# shrew-programmer.net
KiCad netlist of a schematic drawn in EAGLE
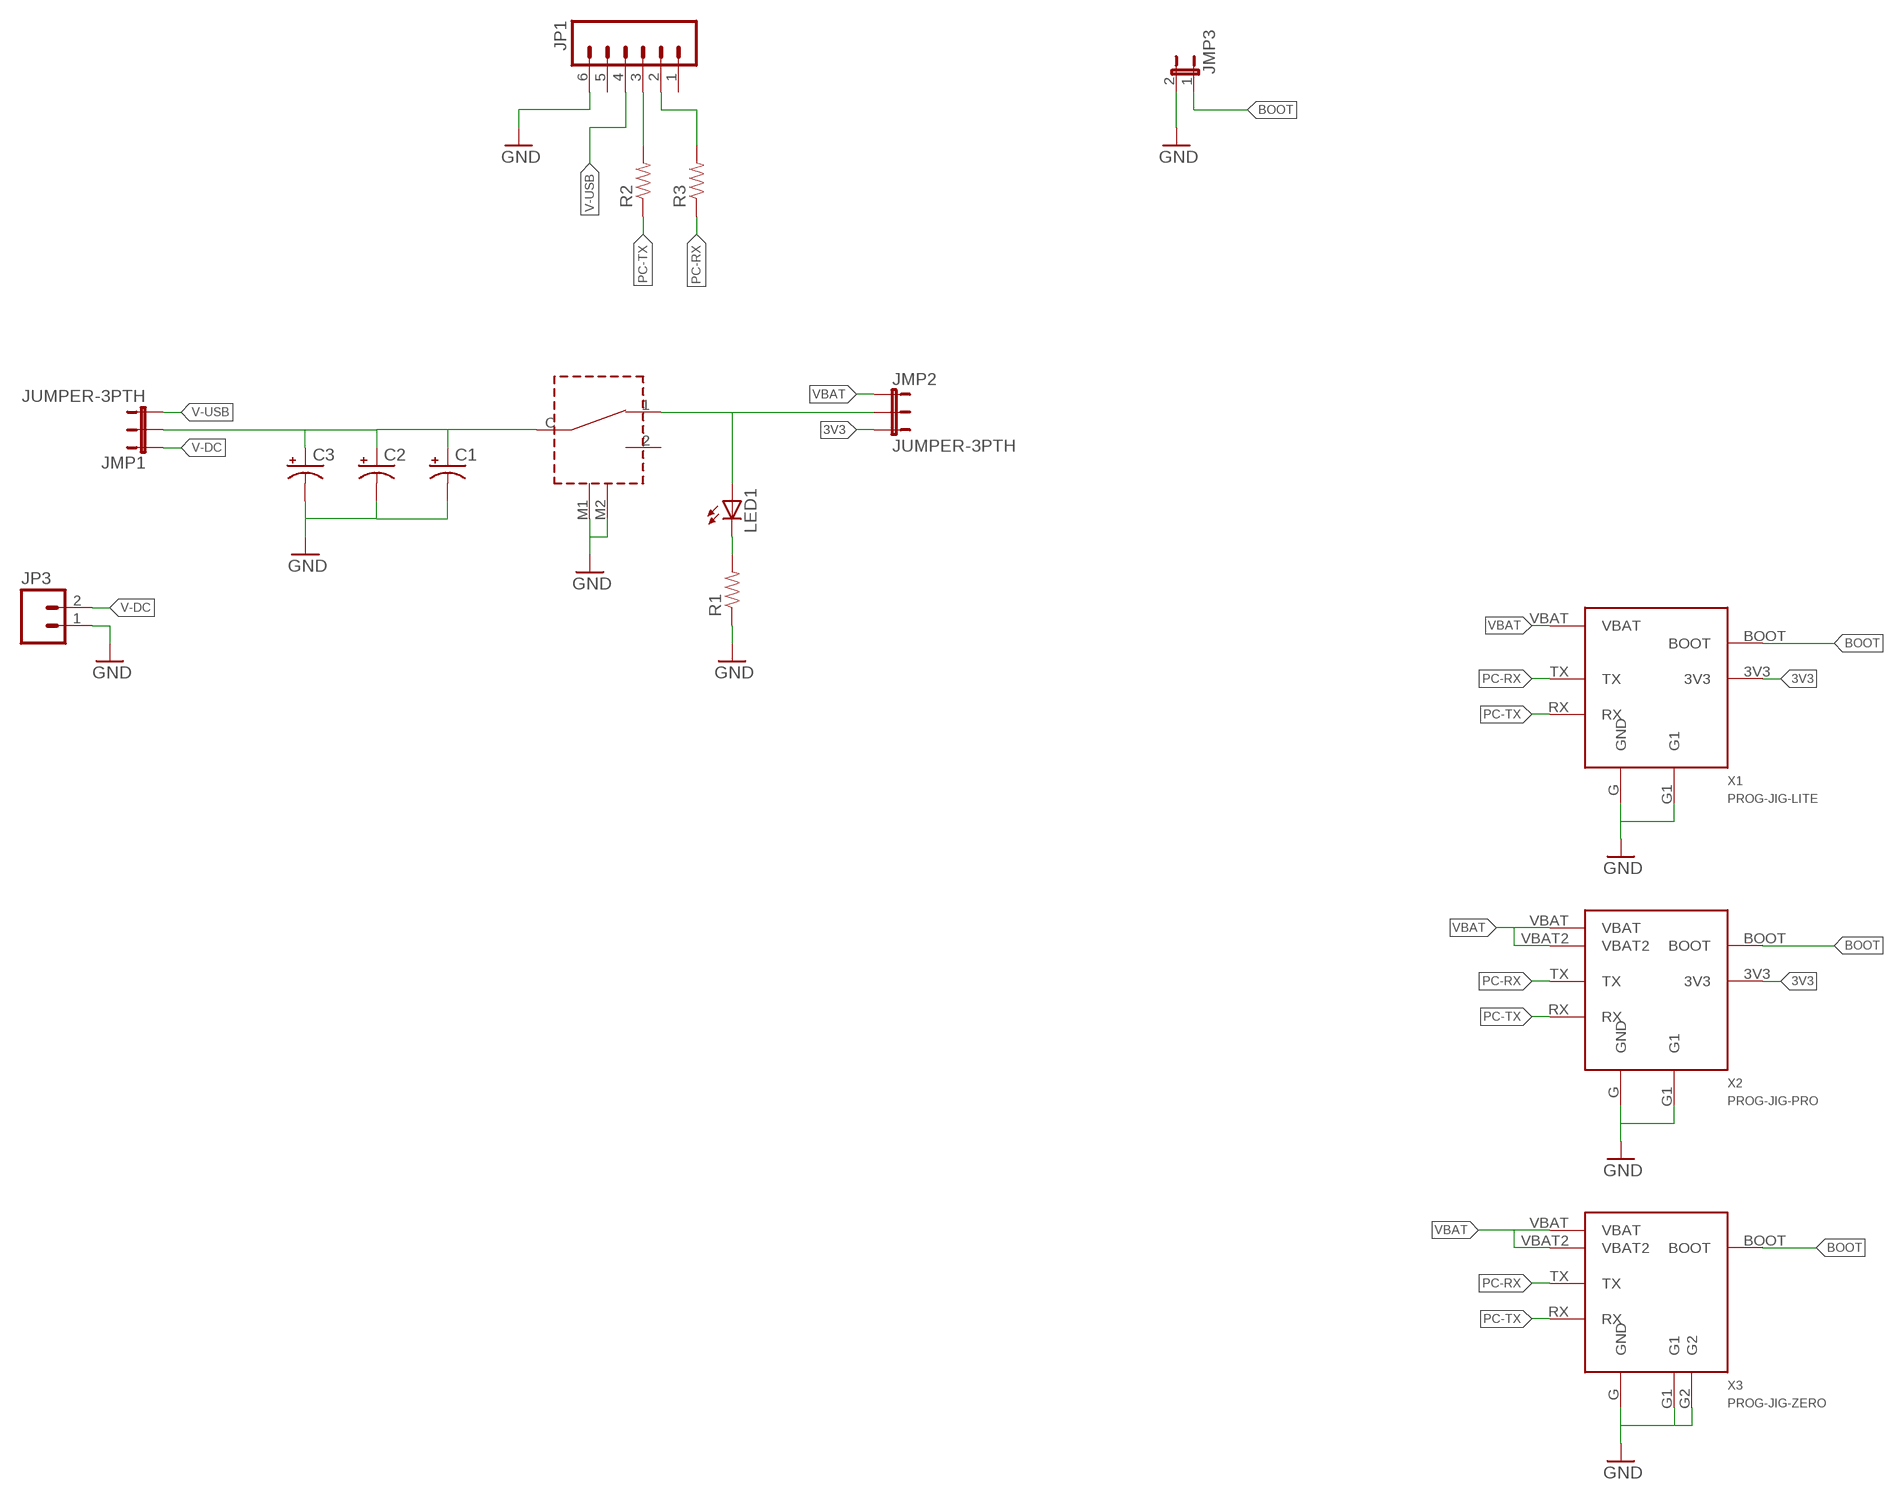
[diagram p0: schematic, sheet 1]

(export (version "E")
  (design (tool "Eeschema 10.0.6"))
  (components
    (comp (ref "C1")
      (value "CAP_POLPTH1")
      (footprint "eagle-import:CPOL-RADIAL-100UF-25V")
      (libsource (lib "eagle-import") (part "CAP_POLPTH1"))
    )
    (comp (ref "C2")
      (value "CAP_POLPTH1")
      (footprint "eagle-import:CPOL-RADIAL-100UF-25V")
      (libsource (lib "eagle-import") (part "CAP_POLPTH1"))
    )
    (comp (ref "C3")
      (value "CAP_POLPTH1")
      (footprint "eagle-import:CPOL-RADIAL-100UF-25V")
      (libsource (lib "eagle-import") (part "CAP_POLPTH1"))
    )
    (comp (ref "JMP1")
      (value "JUMPER-3PTH")
      (footprint "eagle-import:1X03")
      (libsource (lib "eagle-import") (part "JUMPER-3PTH"))
    )
    (comp (ref "JMP2")
      (value "JUMPER-3PTH")
      (footprint "eagle-import:1X03")
      (libsource (lib "eagle-import") (part "JUMPER-3PTH"))
    )
    (comp (ref "JMP3")
      (value "JUMPER-2PTH")
      (footprint "eagle-import:1X02")
      (libsource (lib "eagle-import") (part "JUMPER-2PTH"))
    )
    (comp (ref "JP1")
      (value "M06LONGPADS")
      (footprint "eagle-import:1X06_LONGPADS")
      (libsource (lib "eagle-import") (part "M06LONGPADS"))
    )
    (comp (ref "JP3")
      (value "M023.5MM")
      (footprint "eagle-import:SCREWTERMINAL-3.5MM-2")
      (libsource (lib "eagle-import") (part "M023.5MM"))
    )
    (comp (ref "LED1")
      (value "LED1206")
      (footprint "eagle-import:LED-1206")
      (libsource (lib "eagle-import") (part "LED1206"))
    )
    (comp (ref "R1")
      (value "RESISTOR0603-RES")
      (footprint "eagle-import:0603-RES")
      (libsource (lib "eagle-import") (part "RESISTOR0603-RES"))
    )
    (comp (ref "R2")
      (value "RESISTOR0603-RES")
      (footprint "eagle-import:0603-RES")
      (libsource (lib "eagle-import") (part "RESISTOR0603-RES"))
    )
    (comp (ref "R3")
      (value "RESISTOR0603-RES")
      (footprint "eagle-import:0603-RES")
      (libsource (lib "eagle-import") (part "RESISTOR0603-RES"))
    )
    (comp (ref "SW1")
      (value "SWITCH-ROCKER-3PIN-2MNT")
      (footprint "eagle-import:SWITCH-ROCKER-3PIN-2MNT")
      (libsource (lib "eagle-import") (part "SWITCH-ROCKER-3PIN-2MNT"))
    )
    (comp (ref "X1")
      (value "PROG-JIG-LITE")
      (footprint "eagle-import:PROG-JIG-LITE")
      (libsource (lib "eagle-import") (part "PROG-JIG-LITE"))
    )
    (comp (ref "X2")
      (value "PROG-JIG-PRO")
      (footprint "eagle-import:PROG-JIG-PRO")
      (libsource (lib "eagle-import") (part "PROG-JIG-PRO"))
    )
    (comp (ref "X3")
      (value "PROG-JIG-ZERO")
      (footprint "eagle-import:PROG-JIG-ZERO")
      (libsource (lib "eagle-import") (part "PROG-JIG-ZERO"))
    )
  )
  (nets
    (net (code "1") (name "3V3") (class "Default")
      (node (ref "JMP2") (pin "3") (pinfunction "3_3") (pintype "passive"))
      (node (ref "X1") (pin "3V3") (pinfunction "3V3_3V3") (pintype "bidirectional"))
      (node (ref "X2") (pin "3V3") (pinfunction "3V3_3V3") (pintype "bidirectional"))
    )
    (net (code "2") (name "BOOT") (class "Default")
      (node (ref "JMP3") (pin "1") (pinfunction "1_1") (pintype "passive"))
      (node (ref "X1") (pin "BOOT") (pinfunction "BOOT_BOOT") (pintype "bidirectional"))
      (node (ref "X2") (pin "BOOT") (pinfunction "BOOT_BOOT") (pintype "bidirectional"))
      (node (ref "X3") (pin "BOOT") (pinfunction "BOOT_BOOT") (pintype "bidirectional"))
    )
    (net (code "3") (name "GND") (class "Default")
      (node (ref "C1") (pin "2") (pinfunction "-_2") (pintype "passive"))
      (node (ref "C2") (pin "2") (pinfunction "-_2") (pintype "passive"))
      (node (ref "C3") (pin "2") (pinfunction "-_2") (pintype "passive"))
      (node (ref "JMP3") (pin "2") (pinfunction "2_2") (pintype "passive"))
      (node (ref "JP1") (pin "6") (pinfunction "6_6") (pintype "passive"))
      (node (ref "JP3") (pin "1") (pinfunction "1_1") (pintype "passive"))
      (node (ref "R1") (pin "1") (pinfunction "1_1") (pintype "passive"))
      (node (ref "SW1") (pin "M1") (pinfunction "M1_M1") (pintype "bidirectional"))
      (node (ref "SW1") (pin "M2") (pinfunction "M2_M2") (pintype "bidirectional"))
      (node (ref "X1") (pin "G") (pinfunction "GND_G") (pintype "bidirectional"))
      (node (ref "X1") (pin "G1") (pinfunction "G1_G1") (pintype "bidirectional"))
      (node (ref "X2") (pin "G") (pinfunction "GND_G") (pintype "bidirectional"))
      (node (ref "X2") (pin "G1") (pinfunction "G1_G1") (pintype "bidirectional"))
      (node (ref "X3") (pin "G") (pinfunction "GND_G") (pintype "bidirectional"))
      (node (ref "X3") (pin "G1") (pinfunction "G1_G1") (pintype "bidirectional"))
      (node (ref "X3") (pin "G2") (pinfunction "G2_G2") (pintype "bidirectional"))
    )
    (net (code "4") (name "Net-(C1-+)") (class "Default")
      (node (ref "C1") (pin "1") (pinfunction "+_1") (pintype "passive"))
      (node (ref "C2") (pin "1") (pinfunction "+_1") (pintype "passive"))
      (node (ref "C3") (pin "1") (pinfunction "+_1") (pintype "passive"))
      (node (ref "JMP1") (pin "2") (pinfunction "2_2") (pintype "passive"))
      (node (ref "SW1") (pin "C") (pinfunction "C_C") (pintype "bidirectional"))
    )
    (net (code "5") (name "Net-(JMP2-Pad2)") (class "Default")
      (node (ref "JMP2") (pin "2") (pinfunction "2_2") (pintype "passive"))
      (node (ref "LED1") (pin "A") (pinfunction "A_A") (pintype "passive"))
      (node (ref "SW1") (pin "1") (pinfunction "1_1") (pintype "bidirectional"))
    )
    (net (code "6") (name "Net-(JP1-Pad2)") (class "Default")
      (node (ref "JP1") (pin "2") (pinfunction "2_2") (pintype "passive"))
      (node (ref "R3") (pin "2") (pinfunction "2_2") (pintype "passive"))
    )
    (net (code "7") (name "Net-(JP1-Pad3)") (class "Default")
      (node (ref "JP1") (pin "3") (pinfunction "3_3") (pintype "passive"))
      (node (ref "R2") (pin "2") (pinfunction "2_2") (pintype "passive"))
    )
    (net (code "8") (name "Net-(LED1-PadC)") (class "Default")
      (node (ref "LED1") (pin "C") (pinfunction "C_C") (pintype "passive"))
      (node (ref "R1") (pin "2") (pinfunction "2_2") (pintype "passive"))
    )
    (net (code "9") (name "PC-RX") (class "Default")
      (node (ref "R3") (pin "1") (pinfunction "1_1") (pintype "passive"))
      (node (ref "X1") (pin "TX") (pinfunction "TX_TX") (pintype "bidirectional"))
      (node (ref "X2") (pin "TX") (pinfunction "TX_TX") (pintype "bidirectional"))
      (node (ref "X3") (pin "TX") (pinfunction "TX_TX") (pintype "bidirectional"))
    )
    (net (code "10") (name "PC-TX") (class "Default")
      (node (ref "R2") (pin "1") (pinfunction "1_1") (pintype "passive"))
      (node (ref "X1") (pin "RX") (pinfunction "RX_RX") (pintype "bidirectional"))
      (node (ref "X2") (pin "RX") (pinfunction "RX_RX") (pintype "bidirectional"))
      (node (ref "X3") (pin "RX") (pinfunction "RX_RX") (pintype "bidirectional"))
    )
    (net (code "11") (name "V-DC") (class "Default")
      (node (ref "JMP1") (pin "1") (pinfunction "1_1") (pintype "passive"))
      (node (ref "JP3") (pin "2") (pinfunction "2_2") (pintype "passive"))
    )
    (net (code "12") (name "V-USB") (class "Default")
      (node (ref "JMP1") (pin "3") (pinfunction "3_3") (pintype "passive"))
      (node (ref "JP1") (pin "4") (pinfunction "4_4") (pintype "passive"))
    )
    (net (code "13") (name "VBAT") (class "Default")
      (node (ref "JMP2") (pin "1") (pinfunction "1_1") (pintype "passive"))
      (node (ref "X1") (pin "VBAT") (pinfunction "VBAT_VBAT") (pintype "bidirectional"))
      (node (ref "X2") (pin "VBAT") (pinfunction "VBAT_VBAT") (pintype "bidirectional"))
      (node (ref "X2") (pin "VBAT2") (pinfunction "VBAT2_VBAT2") (pintype "bidirectional"))
      (node (ref "X3") (pin "VBAT") (pinfunction "VBAT_VBAT") (pintype "bidirectional"))
      (node (ref "X3") (pin "VBAT2") (pinfunction "VBAT2_VBAT2") (pintype "bidirectional"))
    )
    (net (code "14") (name "unconnected-(JP1-Pad1)") (class "Default")
      (node (ref "JP1") (pin "1") (pinfunction "1_1") (pintype "passive"))
    )
    (net (code "15") (name "unconnected-(JP1-Pad5)") (class "Default")
      (node (ref "JP1") (pin "5") (pinfunction "5_5") (pintype "passive"))
    )
    (net (code "16") (name "unconnected-(SW1-Pad2)") (class "Default")
      (node (ref "SW1") (pin "2") (pinfunction "2_2") (pintype "bidirectional"))
    )
  )
)
